# 51_MCU_Development_board.net
KiCad netlist of a schematic drawn in Altium Designer
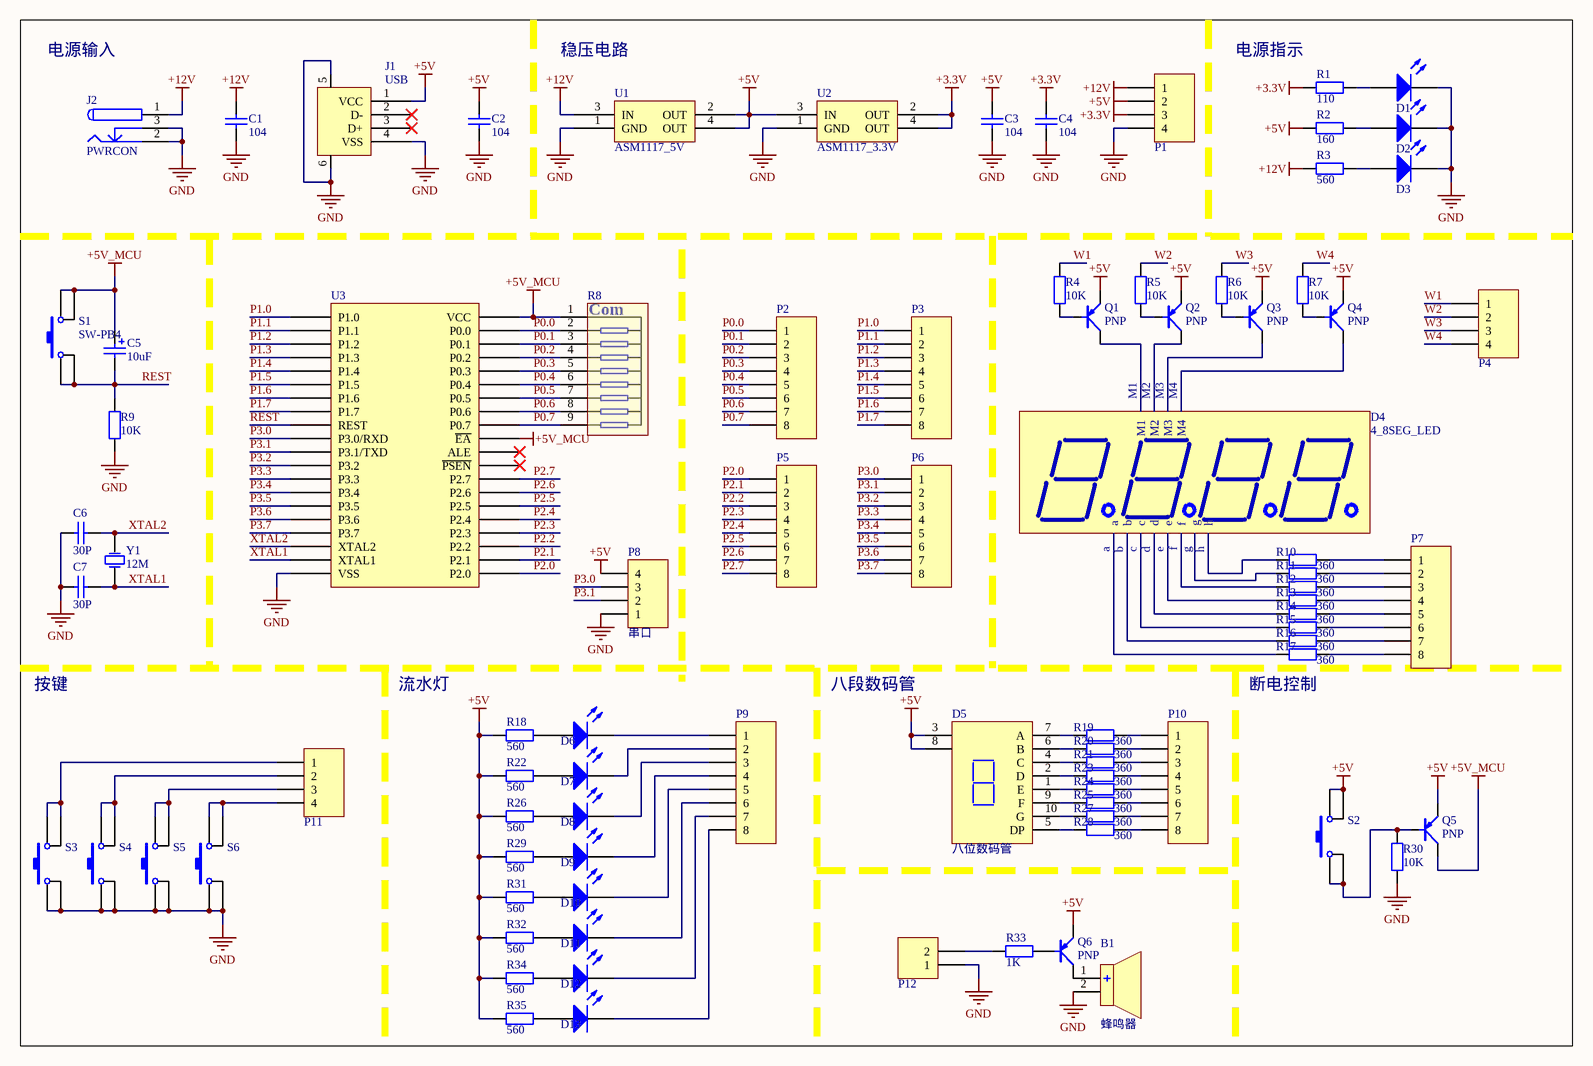
[diagram p0: 51 MCU Development board.SchDoc]

(export (version "E")
  (design (tool "Eeschema 10.0.6"))
  (components
    (comp (ref "B1")
      (value "蜂鸣器")
      (footprint "蜂鸣器")
      (libsource (lib "51 MCU Development board") (part "蜂鸣器"))
    )
    (comp (ref "C1")
      (value "104")
      (footprint "C-RAD-0805")
      (description "无极性电容")
      (fields (field (name "Comment") "Cap") (field (name "PUBLISHER") "Altium Limited"))
      (libsource (lib "常用库文件") (part "Cap"))
    )
    (comp (ref "C2")
      (value "104")
      (footprint "C-RAD-0805")
      (description "无极性电容")
      (fields (field (name "Comment") "Cap") (field (name "PUBLISHER") "Altium Limited"))
      (libsource (lib "常用库文件") (part "Cap"))
    )
    (comp (ref "C3")
      (value "104")
      (footprint "C-RAD-0805")
      (description "无极性电容")
      (fields (field (name "Comment") "Cap") (field (name "PUBLISHER") "Altium Limited"))
      (libsource (lib "常用库文件") (part "Cap"))
    )
    (comp (ref "C4")
      (value "104")
      (footprint "C-RAD-0805")
      (description "无极性电容")
      (fields (field (name "Comment") "Cap") (field (name "PUBLISHER") "Altium Limited"))
      (libsource (lib "常用库文件") (part "Cap"))
    )
    (comp (ref "C5")
      (value "10uF")
      (footprint "10UF")
      (description "Polarized Capacitor (Radial)")
      (fields (field (name "Comment") "Cap Pol1") (field (name "PUBLISHER") "Altium Limited"))
      (libsource (lib "51 MCU Development board") (part "Cap Pol1"))
    )
    (comp (ref "C6")
      (value "30P")
      (footprint "C-RAD")
      (description "无极性电容")
      (fields (field (name "Comment") "Cap") (field (name "PUBLISHER") "Altium Limited"))
      (libsource (lib "常用库文件") (part "Cap"))
    )
    (comp (ref "C7")
      (value "30P")
      (footprint "C-RAD")
      (description "无极性电容")
      (fields (field (name "Comment") "Cap") (field (name "PUBLISHER") "Altium Limited"))
      (libsource (lib "常用库文件") (part "Cap"))
    )
    (comp (ref "D1")
      (value "LED0")
      (footprint "LED_0805")
      (description "发光二极管")
      (fields (field (name "PUBLISHER") "Altium Limited"))
      (libsource (lib "常用库文件") (part "LED0"))
    )
    (comp (ref "D2")
      (value "LED0")
      (footprint "LED_0805")
      (description "发光二极管")
      (fields (field (name "PUBLISHER") "Altium Limited"))
      (libsource (lib "常用库文件") (part "LED0"))
    )
    (comp (ref "D3")
      (value "LED0")
      (footprint "LED_0805")
      (description "发光二极管")
      (fields (field (name "PUBLISHER") "Altium Limited"))
      (libsource (lib "常用库文件") (part "LED0"))
    )
    (comp (ref "D4")
      (value "4_8SEG_LED")
      (footprint "4BIT_8SEG_LED")
      (libsource (lib "51 MCU Development board") (part "4_8SEG_LED"))
    )
    (comp (ref "D5")
      (value "八位数码管")
      (footprint "八位数码管")
      (libsource (lib "51 MCU Development board") (part "八位数码管"))
    )
    (comp (ref "D6")
      (value "LED0")
      (footprint "LED直插")
      (description "发光二极管")
      (fields (field (name "PUBLISHER") "Altium Limited"))
      (libsource (lib "常用库文件") (part "LED0"))
    )
    (comp (ref "D7")
      (value "LED0")
      (footprint "LED直插")
      (description "发光二极管")
      (fields (field (name "PUBLISHER") "Altium Limited"))
      (libsource (lib "常用库文件") (part "LED0"))
    )
    (comp (ref "D8")
      (value "LED0")
      (footprint "LED直插")
      (description "发光二极管")
      (fields (field (name "PUBLISHER") "Altium Limited"))
      (libsource (lib "常用库文件") (part "LED0"))
    )
    (comp (ref "D9")
      (value "LED0")
      (footprint "LED直插")
      (description "发光二极管")
      (fields (field (name "PUBLISHER") "Altium Limited"))
      (libsource (lib "常用库文件") (part "LED0"))
    )
    (comp (ref "D10")
      (value "LED0")
      (footprint "LED直插")
      (description "发光二极管")
      (fields (field (name "PUBLISHER") "Altium Limited"))
      (libsource (lib "常用库文件") (part "LED0"))
    )
    (comp (ref "D11")
      (value "LED0")
      (footprint "LED直插")
      (description "发光二极管")
      (fields (field (name "PUBLISHER") "Altium Limited"))
      (libsource (lib "常用库文件") (part "LED0"))
    )
    (comp (ref "D12")
      (value "LED0")
      (footprint "LED直插")
      (description "发光二极管")
      (fields (field (name "PUBLISHER") "Altium Limited"))
      (libsource (lib "常用库文件") (part "LED0"))
    )
    (comp (ref "D13")
      (value "LED0")
      (footprint "LED直插")
      (description "发光二极管")
      (fields (field (name "PUBLISHER") "Altium Limited"))
      (libsource (lib "常用库文件") (part "LED0"))
    )
    (comp (ref "J1")
      (value "USB")
      (footprint "USB_A1")
      (description "USB接口")
      (libsource (lib "常用库文件") (part "USB"))
    )
    (comp (ref "J2")
      (value "PWRCON")
      (footprint "DC-005")
      (description "直流电源端子")
      (fields (field (name "PUBLISHER") "Altium Limited"))
      (libsource (lib "常用库文件") (part "PWRCON"))
    )
    (comp (ref "P1")
      (value "Header 4")
      (footprint "HDR4X1_A")
      (description "接插件")
      (fields (field (name "PUBLISHER") "Altium Limited"))
      (libsource (lib "常用库文件") (part "Header 4"))
    )
    (comp (ref "P2")
      (value "Header 8")
      (footprint "HDR1X8")
      (description "Header, 8-Pin")
      (fields (field (name "PUBLISHER") "Altium Limited"))
      (libsource (lib "Miscellaneous Connectors") (part "Header 8"))
    )
    (comp (ref "P3")
      (value "Header 8")
      (footprint "HDR1X8")
      (description "Header, 8-Pin")
      (fields (field (name "PUBLISHER") "Altium Limited"))
      (libsource (lib "Miscellaneous Connectors") (part "Header 8"))
    )
    (comp (ref "P4")
      (value "Header 4")
      (footprint "HDR4X1_A")
      (description "接插件")
      (fields (field (name "PUBLISHER") "Altium Limited"))
      (libsource (lib "常用库文件") (part "Header 4"))
    )
    (comp (ref "P5")
      (value "Header 8")
      (footprint "HDR1X8")
      (description "Header, 8-Pin")
      (fields (field (name "PUBLISHER") "Altium Limited"))
      (libsource (lib "Miscellaneous Connectors") (part "Header 8"))
    )
    (comp (ref "P6")
      (value "Header 8")
      (footprint "HDR1X8")
      (description "Header, 8-Pin")
      (fields (field (name "PUBLISHER") "Altium Limited"))
      (libsource (lib "Miscellaneous Connectors") (part "Header 8"))
    )
    (comp (ref "P7")
      (value "Header 8")
      (footprint "HDR1X8")
      (description "Header, 8-Pin")
      (fields (field (name "PUBLISHER") "Altium Limited"))
      (libsource (lib "Miscellaneous Connectors") (part "Header 8"))
    )
    (comp (ref "P8")
      (value "串口")
      (footprint "HDR4X1_A")
      (description "接插件")
      (fields (field (name "PUBLISHER") "Altium Limited"))
      (libsource (lib "") (part "Header 4_1"))
    )
    (comp (ref "P9")
      (value "Header 8")
      (footprint "HDR1X8")
      (description "Header, 8-Pin")
      (fields (field (name "PUBLISHER") "Altium Limited"))
      (libsource (lib "Miscellaneous Connectors") (part "Header 8"))
    )
    (comp (ref "P10")
      (value "Header 8")
      (footprint "HDR1X8")
      (description "Header, 8-Pin")
      (fields (field (name "PUBLISHER") "Altium Limited"))
      (libsource (lib "Miscellaneous Connectors") (part "Header 8"))
    )
    (comp (ref "P11")
      (value "Header 4")
      (footprint "HDR4X1_A")
      (description "接插件")
      (fields (field (name "PUBLISHER") "Altium Limited"))
      (libsource (lib "常用库文件") (part "Header 4"))
    )
    (comp (ref "P12")
      (value "Header 2")
      (footprint "HDR2X1_A")
      (description "接插件")
      (fields (field (name "PUBLISHER") "Altium Limited"))
      (libsource (lib "常用库文件") (part "Header 2"))
    )
    (comp (ref "Q1")
      (value "PNP")
      (footprint "TO-92")
      (libsource (lib "51 MCU Development board") (part "PNP"))
    )
    (comp (ref "Q2")
      (value "PNP")
      (footprint "TO-92")
      (libsource (lib "51 MCU Development board") (part "PNP"))
    )
    (comp (ref "Q3")
      (value "PNP")
      (footprint "TO-92")
      (libsource (lib "51 MCU Development board") (part "PNP"))
    )
    (comp (ref "Q4")
      (value "PNP")
      (footprint "TO-92")
      (libsource (lib "51 MCU Development board") (part "PNP"))
    )
    (comp (ref "Q5")
      (value "PNP")
      (footprint "TO-92")
      (libsource (lib "51 MCU Development board") (part "PNP"))
    )
    (comp (ref "Q6")
      (value "PNP")
      (footprint "TO-92")
      (libsource (lib "51 MCU Development board") (part "PNP"))
    )
    (comp (ref "R1")
      (value "110")
      (footprint "0805-1")
      (description "贴片电阻")
      (fields (field (name "Comment") "Res1") (field (name "PUBLISHER") "Altium Limited"))
      (libsource (lib "常用库文件") (part "Res1"))
    )
    (comp (ref "R2")
      (value "160")
      (footprint "0805-1")
      (description "贴片电阻")
      (fields (field (name "Comment") "Res1") (field (name "PUBLISHER") "Altium Limited"))
      (libsource (lib "常用库文件") (part "Res1"))
    )
    (comp (ref "R3")
      (value "560")
      (footprint "0805-1")
      (description "贴片电阻")
      (fields (field (name "Comment") "Res1") (field (name "PUBLISHER") "Altium Limited"))
      (libsource (lib "常用库文件") (part "Res1"))
    )
    (comp (ref "R4")
      (value "10K")
      (footprint "0805-1")
      (description "贴片电阻")
      (fields (field (name "Comment") "Res1") (field (name "PUBLISHER") "Altium Limited"))
      (libsource (lib "") (part "Res1_1"))
    )
    (comp (ref "R5")
      (value "10K")
      (footprint "0805-1")
      (description "贴片电阻")
      (fields (field (name "Comment") "Res1") (field (name "PUBLISHER") "Altium Limited"))
      (libsource (lib "") (part "Res1_1"))
    )
    (comp (ref "R6")
      (value "10K")
      (footprint "0805-1")
      (description "贴片电阻")
      (fields (field (name "Comment") "Res1") (field (name "PUBLISHER") "Altium Limited"))
      (libsource (lib "") (part "Res1_1"))
    )
    (comp (ref "R7")
      (value "10K")
      (footprint "0805-1")
      (description "贴片电阻")
      (fields (field (name "Comment") "Res1") (field (name "PUBLISHER") "Altium Limited"))
      (libsource (lib "") (part "Res1_1"))
    )
    (comp (ref "R8")
      (value "RES10")
      (footprint "SIP9")
      (libsource (lib "51 MCU Development board") (part "RES10"))
    )
    (comp (ref "R9")
      (value "10K")
      (footprint "0805-1")
      (description "贴片电阻")
      (fields (field (name "Comment") "Res1") (field (name "PUBLISHER") "Altium Limited"))
      (libsource (lib "") (part "Res1_1"))
    )
    (comp (ref "R10")
      (value "360")
      (footprint "0805-1")
      (description "贴片电阻")
      (fields (field (name "Comment") "Res1") (field (name "PUBLISHER") "Altium Limited"))
      (libsource (lib "") (part "Res1_2"))
    )
    (comp (ref "R11")
      (value "360")
      (footprint "0805-1")
      (description "贴片电阻")
      (fields (field (name "Comment") "Res1") (field (name "PUBLISHER") "Altium Limited"))
      (libsource (lib "") (part "Res1_2"))
    )
    (comp (ref "R12")
      (value "360")
      (footprint "0805-1")
      (description "贴片电阻")
      (fields (field (name "Comment") "Res1") (field (name "PUBLISHER") "Altium Limited"))
      (libsource (lib "") (part "Res1_2"))
    )
    (comp (ref "R13")
      (value "360")
      (footprint "0805-1")
      (description "贴片电阻")
      (fields (field (name "Comment") "Res1") (field (name "PUBLISHER") "Altium Limited"))
      (libsource (lib "") (part "Res1_2"))
    )
    (comp (ref "R14")
      (value "360")
      (footprint "0805-1")
      (description "贴片电阻")
      (fields (field (name "Comment") "Res1") (field (name "PUBLISHER") "Altium Limited"))
      (libsource (lib "") (part "Res1_2"))
    )
    (comp (ref "R15")
      (value "360")
      (footprint "0805-1")
      (description "贴片电阻")
      (fields (field (name "Comment") "Res1") (field (name "PUBLISHER") "Altium Limited"))
      (libsource (lib "") (part "Res1_2"))
    )
    (comp (ref "R16")
      (value "360")
      (footprint "0805-1")
      (description "贴片电阻")
      (fields (field (name "Comment") "Res1") (field (name "PUBLISHER") "Altium Limited"))
      (libsource (lib "") (part "Res1_2"))
    )
    (comp (ref "R17")
      (value "360")
      (footprint "0805-1")
      (description "贴片电阻")
      (fields (field (name "Comment") "Res1") (field (name "PUBLISHER") "Altium Limited"))
      (libsource (lib "") (part "Res1_2"))
    )
    (comp (ref "R18")
      (value "560")
      (footprint "0805-1")
      (description "贴片电阻")
      (fields (field (name "Comment") "Res1") (field (name "PUBLISHER") "Altium Limited"))
      (libsource (lib "常用库文件") (part "Res1"))
    )
    (comp (ref "R19")
      (value "360")
      (footprint "0805-1")
      (description "贴片电阻")
      (fields (field (name "Comment") "Res1") (field (name "PUBLISHER") "Altium Limited"))
      (libsource (lib "") (part "Res1_2"))
    )
    (comp (ref "R20")
      (value "360")
      (footprint "0805-1")
      (description "贴片电阻")
      (fields (field (name "Comment") "Res1") (field (name "PUBLISHER") "Altium Limited"))
      (libsource (lib "") (part "Res1_2"))
    )
    (comp (ref "R21")
      (value "360")
      (footprint "0805-1")
      (description "贴片电阻")
      (fields (field (name "Comment") "Res1") (field (name "PUBLISHER") "Altium Limited"))
      (libsource (lib "") (part "Res1_2"))
    )
    (comp (ref "R22")
      (value "560")
      (footprint "0805-1")
      (description "贴片电阻")
      (fields (field (name "Comment") "Res1") (field (name "PUBLISHER") "Altium Limited"))
      (libsource (lib "常用库文件") (part "Res1"))
    )
    (comp (ref "R23")
      (value "360")
      (footprint "0805-1")
      (description "贴片电阻")
      (fields (field (name "Comment") "Res1") (field (name "PUBLISHER") "Altium Limited"))
      (libsource (lib "") (part "Res1_2"))
    )
    (comp (ref "R24")
      (value "360")
      (footprint "0805-1")
      (description "贴片电阻")
      (fields (field (name "Comment") "Res1") (field (name "PUBLISHER") "Altium Limited"))
      (libsource (lib "") (part "Res1_2"))
    )
    (comp (ref "R25")
      (value "360")
      (footprint "0805-1")
      (description "贴片电阻")
      (fields (field (name "Comment") "Res1") (field (name "PUBLISHER") "Altium Limited"))
      (libsource (lib "") (part "Res1_2"))
    )
    (comp (ref "R26")
      (value "560")
      (footprint "0805-1")
      (description "贴片电阻")
      (fields (field (name "Comment") "Res1") (field (name "PUBLISHER") "Altium Limited"))
      (libsource (lib "常用库文件") (part "Res1"))
    )
    (comp (ref "R27")
      (value "360")
      (footprint "0805-1")
      (description "贴片电阻")
      (fields (field (name "Comment") "Res1") (field (name "PUBLISHER") "Altium Limited"))
      (libsource (lib "") (part "Res1_2"))
    )
    (comp (ref "R28")
      (value "360")
      (footprint "0805-1")
      (description "贴片电阻")
      (fields (field (name "Comment") "Res1") (field (name "PUBLISHER") "Altium Limited"))
      (libsource (lib "") (part "Res1_2"))
    )
    (comp (ref "R29")
      (value "560")
      (footprint "0805-1")
      (description "贴片电阻")
      (fields (field (name "Comment") "Res1") (field (name "PUBLISHER") "Altium Limited"))
      (libsource (lib "常用库文件") (part "Res1"))
    )
    (comp (ref "R30")
      (value "10K")
      (footprint "0805-1")
      (description "贴片电阻")
      (fields (field (name "Comment") "Res1") (field (name "PUBLISHER") "Altium Limited"))
      (libsource (lib "") (part "Res1_1"))
    )
    (comp (ref "R31")
      (value "560")
      (footprint "0805-1")
      (description "贴片电阻")
      (fields (field (name "Comment") "Res1") (field (name "PUBLISHER") "Altium Limited"))
      (libsource (lib "常用库文件") (part "Res1"))
    )
    (comp (ref "R32")
      (value "560")
      (footprint "0805-1")
      (description "贴片电阻")
      (fields (field (name "Comment") "Res1") (field (name "PUBLISHER") "Altium Limited"))
      (libsource (lib "常用库文件") (part "Res1"))
    )
    (comp (ref "R33")
      (value "1K")
      (footprint "0805-1")
      (description "贴片电阻")
      (fields (field (name "Comment") "Res1") (field (name "PUBLISHER") "Altium Limited"))
      (libsource (lib "") (part "Res1_2"))
    )
    (comp (ref "R34")
      (value "560")
      (footprint "0805-1")
      (description "贴片电阻")
      (fields (field (name "Comment") "Res1") (field (name "PUBLISHER") "Altium Limited"))
      (libsource (lib "常用库文件") (part "Res1"))
    )
    (comp (ref "R35")
      (value "560")
      (footprint "0805-1")
      (description "贴片电阻")
      (fields (field (name "Comment") "Res1") (field (name "PUBLISHER") "Altium Limited"))
      (libsource (lib "常用库文件") (part "Res1"))
    )
    (comp (ref "S1")
      (value "SW-PB4")
      (footprint "AN66")
      (description "微动开关")
      (fields (field (name "PUBLISHER") "Altium Limited"))
      (libsource (lib "常用库文件") (part "SW-PB4"))
    )
    (comp (ref "S2")
      (value "SW-PB4")
      (footprint "AN66")
      (description "微动开关")
      (fields (field (name "PUBLISHER") "Altium Limited"))
      (libsource (lib "常用库文件") (part "SW-PB4"))
    )
    (comp (ref "S3")
      (value "SW-PB4")
      (footprint "AN66")
      (description "微动开关")
      (fields (field (name "PUBLISHER") "Altium Limited"))
      (libsource (lib "常用库文件") (part "SW-PB4"))
    )
    (comp (ref "S4")
      (value "SW-PB4")
      (footprint "AN66")
      (description "微动开关")
      (fields (field (name "PUBLISHER") "Altium Limited"))
      (libsource (lib "常用库文件") (part "SW-PB4"))
    )
    (comp (ref "S5")
      (value "SW-PB4")
      (footprint "AN66")
      (description "微动开关")
      (fields (field (name "PUBLISHER") "Altium Limited"))
      (libsource (lib "常用库文件") (part "SW-PB4"))
    )
    (comp (ref "S6")
      (value "SW-PB4")
      (footprint "AN66")
      (description "微动开关")
      (fields (field (name "PUBLISHER") "Altium Limited"))
      (libsource (lib "常用库文件") (part "SW-PB4"))
    )
    (comp (ref "U1")
      (value "ASM1117_5V")
      (footprint "SOT-223")
      (description "3.3V稳压芯片")
      (libsource (lib "常用库文件") (part "ASM1117"))
    )
    (comp (ref "U2")
      (value "ASM1117_3.3V")
      (footprint "SOT-223")
      (description "3.3V稳压芯片")
      (libsource (lib "常用库文件") (part "ASM1117"))
    )
    (comp (ref "U3")
      (value "STC89C52RC")
      (footprint "DIP-40W")
      (libsource (lib "51 MCU Development board") (part "STC89C52RC"))
    )
    (comp (ref "Y1")
      (value "12M")
      (footprint "X-HC49U")
      (description "晶振")
      (fields (field (name "Comment") "XTAL") (field (name "PUBLISHER") "Altium Limited"))
      (libsource (lib "常用库文件") (part "XTAL"))
    )
  )
  (nets
    (net (code "1") (name "+3.3V") (class "Default")
      (node (ref "C4") (pin "2") (pinfunction "2_2") (pintype "passive"))
      (node (ref "P1") (pin "3") (pinfunction "3_3") (pintype "passive"))
      (node (ref "R1") (pin "1") (pinfunction "1_1") (pintype "passive"))
      (node (ref "U2") (pin "2") (pinfunction "OUT_2") (pintype "passive"))
      (node (ref "U2") (pin "4") (pinfunction "OUT_4") (pintype "passive"))
    )
    (net (code "2") (name "+5V") (class "Default")
      (node (ref "C2") (pin "2") (pinfunction "2_2") (pintype "passive"))
      (node (ref "C3") (pin "2") (pinfunction "2_2") (pintype "passive"))
      (node (ref "D5") (pin "3") (pinfunction "3_3") (pintype "passive"))
      (node (ref "D5") (pin "8") (pinfunction "8_8") (pintype "passive"))
      (node (ref "J1") (pin "1") (pinfunction "VCC_1") (pintype "passive"))
      (node (ref "P1") (pin "2") (pinfunction "2_2") (pintype "passive"))
      (node (ref "P8") (pin "4") (pinfunction "4_4") (pintype "passive"))
      (node (ref "Q1") (pin "E") (pinfunction "e_E") (pintype "passive"))
      (node (ref "Q2") (pin "E") (pinfunction "e_E") (pintype "passive"))
      (node (ref "Q3") (pin "E") (pinfunction "e_E") (pintype "passive"))
      (node (ref "Q4") (pin "E") (pinfunction "e_E") (pintype "passive"))
      (node (ref "Q5") (pin "E") (pinfunction "e_E") (pintype "passive"))
      (node (ref "Q6") (pin "E") (pinfunction "e_E") (pintype "passive"))
      (node (ref "R18") (pin "1") (pinfunction "1_1") (pintype "passive"))
      (node (ref "R2") (pin "1") (pinfunction "1_1") (pintype "passive"))
      (node (ref "R22") (pin "1") (pinfunction "1_1") (pintype "passive"))
      (node (ref "R26") (pin "1") (pinfunction "1_1") (pintype "passive"))
      (node (ref "R29") (pin "1") (pinfunction "1_1") (pintype "passive"))
      (node (ref "R31") (pin "1") (pinfunction "1_1") (pintype "passive"))
      (node (ref "R32") (pin "1") (pinfunction "1_1") (pintype "passive"))
      (node (ref "R34") (pin "1") (pinfunction "1_1") (pintype "passive"))
      (node (ref "R35") (pin "1") (pinfunction "1_1") (pintype "passive"))
      (node (ref "S2") (pin "2") (pinfunction "2_2") (pintype "passive"))
      (node (ref "S2") (pin "3") (pinfunction "3_3") (pintype "passive"))
      (node (ref "U1") (pin "2") (pinfunction "OUT_2") (pintype "passive"))
      (node (ref "U1") (pin "4") (pinfunction "OUT_4") (pintype "passive"))
      (node (ref "U2") (pin "3") (pinfunction "IN_3") (pintype "passive"))
    )
    (net (code "3") (name "+5V_MCU") (class "Default")
      (node (ref "C5") (pin "1") (pinfunction "1_1") (pintype "passive"))
      (node (ref "Q5") (pin "C") (pinfunction "c_C") (pintype "passive"))
      (node (ref "R8") (pin "1") (pinfunction "Com_1") (pintype "passive"))
      (node (ref "S1") (pin "2") (pinfunction "2_2") (pintype "passive"))
      (node (ref "S1") (pin "3") (pinfunction "3_3") (pintype "passive"))
      (node (ref "U3") (pin "31") (pinfunction "~{EA}_31") (pintype "power_in"))
      (node (ref "U3") (pin "40") (pinfunction "VCC_40") (pintype "power_in"))
    )
    (net (code "4") (name "+12V") (class "Default")
      (node (ref "C1") (pin "2") (pinfunction "2_2") (pintype "passive"))
      (node (ref "J2") (pin "1") (pinfunction "1_1") (pintype "power_in"))
      (node (ref "P1") (pin "1") (pinfunction "1_1") (pintype "passive"))
      (node (ref "R3") (pin "1") (pinfunction "1_1") (pintype "passive"))
      (node (ref "U1") (pin "3") (pinfunction "IN_3") (pintype "passive"))
    )
    (net (code "5") (name "/P0.0") (class "Default")
      (node (ref "P2") (pin "1") (pinfunction "1_1") (pintype "passive"))
      (node (ref "R8") (pin "2") (pinfunction "2_2") (pintype "passive"))
      (node (ref "U3") (pin "39") (pinfunction "P0.0_39") (pintype "power_in"))
    )
    (net (code "6") (name "/P0.1") (class "Default")
      (node (ref "P2") (pin "2") (pinfunction "2_2") (pintype "passive"))
      (node (ref "R8") (pin "3") (pinfunction "3_3") (pintype "passive"))
      (node (ref "U3") (pin "38") (pinfunction "P0.1_38") (pintype "power_in"))
    )
    (net (code "7") (name "/P0.2") (class "Default")
      (node (ref "P2") (pin "3") (pinfunction "3_3") (pintype "passive"))
      (node (ref "R8") (pin "4") (pinfunction "4_4") (pintype "passive"))
      (node (ref "U3") (pin "37") (pinfunction "P0.2_37") (pintype "power_in"))
    )
    (net (code "8") (name "/P0.3") (class "Default")
      (node (ref "P2") (pin "4") (pinfunction "4_4") (pintype "passive"))
      (node (ref "R8") (pin "5") (pinfunction "5_5") (pintype "passive"))
      (node (ref "U3") (pin "36") (pinfunction "P0.3_36") (pintype "power_in"))
    )
    (net (code "9") (name "/P0.4") (class "Default")
      (node (ref "P2") (pin "5") (pinfunction "5_5") (pintype "passive"))
      (node (ref "R8") (pin "6") (pinfunction "6_6") (pintype "passive"))
      (node (ref "U3") (pin "35") (pinfunction "P0.4_35") (pintype "power_in"))
    )
    (net (code "10") (name "/P0.5") (class "Default")
      (node (ref "P2") (pin "6") (pinfunction "6_6") (pintype "passive"))
      (node (ref "R8") (pin "7") (pinfunction "7_7") (pintype "passive"))
      (node (ref "U3") (pin "34") (pinfunction "P0.5_34") (pintype "power_in"))
    )
    (net (code "11") (name "/P0.6") (class "Default")
      (node (ref "P2") (pin "7") (pinfunction "7_7") (pintype "passive"))
      (node (ref "R8") (pin "8") (pinfunction "8_8") (pintype "passive"))
      (node (ref "U3") (pin "33") (pinfunction "P0.6_33") (pintype "power_in"))
    )
    (net (code "12") (name "/P0.7") (class "Default")
      (node (ref "P2") (pin "8") (pinfunction "8_8") (pintype "passive"))
      (node (ref "R8") (pin "9") (pinfunction "9_9") (pintype "passive"))
      (node (ref "U3") (pin "32") (pinfunction "P0.7_32") (pintype "power_in"))
    )
    (net (code "13") (name "/P1.0") (class "Default")
      (node (ref "P3") (pin "1") (pinfunction "1_1") (pintype "passive"))
      (node (ref "U3") (pin "1") (pinfunction "P1.0_1") (pintype "power_in"))
    )
    (net (code "14") (name "/P1.1") (class "Default")
      (node (ref "P3") (pin "2") (pinfunction "2_2") (pintype "passive"))
      (node (ref "U3") (pin "2") (pinfunction "P1.1_2") (pintype "power_in"))
    )
    (net (code "15") (name "/P1.2") (class "Default")
      (node (ref "P3") (pin "3") (pinfunction "3_3") (pintype "passive"))
      (node (ref "U3") (pin "3") (pinfunction "P1.2_3") (pintype "power_in"))
    )
    (net (code "16") (name "/P1.3") (class "Default")
      (node (ref "P3") (pin "4") (pinfunction "4_4") (pintype "passive"))
      (node (ref "U3") (pin "4") (pinfunction "P1.3_4") (pintype "power_in"))
    )
    (net (code "17") (name "/P1.4") (class "Default")
      (node (ref "P3") (pin "5") (pinfunction "5_5") (pintype "passive"))
      (node (ref "U3") (pin "5") (pinfunction "P1.4_5") (pintype "power_in"))
    )
    (net (code "18") (name "/P1.5") (class "Default")
      (node (ref "P3") (pin "6") (pinfunction "6_6") (pintype "passive"))
      (node (ref "U3") (pin "6") (pinfunction "P1.5_6") (pintype "power_in"))
    )
    (net (code "19") (name "/P1.6") (class "Default")
      (node (ref "P3") (pin "7") (pinfunction "7_7") (pintype "passive"))
      (node (ref "U3") (pin "7") (pinfunction "P1.6_7") (pintype "power_in"))
    )
    (net (code "20") (name "/P1.7") (class "Default")
      (node (ref "P3") (pin "8") (pinfunction "8_8") (pintype "passive"))
      (node (ref "U3") (pin "8") (pinfunction "P1.7_8") (pintype "power_in"))
    )
    (net (code "21") (name "/P2.0") (class "Default")
      (node (ref "P5") (pin "1") (pinfunction "1_1") (pintype "passive"))
      (node (ref "U3") (pin "21") (pinfunction "P2.0_21") (pintype "power_in"))
    )
    (net (code "22") (name "/P2.1") (class "Default")
      (node (ref "P5") (pin "2") (pinfunction "2_2") (pintype "passive"))
      (node (ref "U3") (pin "22") (pinfunction "P2.1_22") (pintype "power_in"))
    )
    (net (code "23") (name "/P2.2") (class "Default")
      (node (ref "P5") (pin "3") (pinfunction "3_3") (pintype "passive"))
      (node (ref "U3") (pin "23") (pinfunction "P2.2_23") (pintype "power_in"))
    )
    (net (code "24") (name "/P2.3") (class "Default")
      (node (ref "P5") (pin "4") (pinfunction "4_4") (pintype "passive"))
      (node (ref "U3") (pin "24") (pinfunction "P2.3_24") (pintype "power_in"))
    )
    (net (code "25") (name "/P2.4") (class "Default")
      (node (ref "P5") (pin "5") (pinfunction "5_5") (pintype "passive"))
      (node (ref "U3") (pin "25") (pinfunction "P2.4_25") (pintype "power_in"))
    )
    (net (code "26") (name "/P2.5") (class "Default")
      (node (ref "P5") (pin "6") (pinfunction "6_6") (pintype "passive"))
      (node (ref "U3") (pin "26") (pinfunction "P2.5_26") (pintype "power_in"))
    )
    (net (code "27") (name "/P2.6") (class "Default")
      (node (ref "P5") (pin "7") (pinfunction "7_7") (pintype "passive"))
      (node (ref "U3") (pin "27") (pinfunction "P2.6_27") (pintype "power_in"))
    )
    (net (code "28") (name "/P2.7") (class "Default")
      (node (ref "P5") (pin "8") (pinfunction "8_8") (pintype "passive"))
      (node (ref "U3") (pin "28") (pinfunction "P2.7_28") (pintype "power_in"))
    )
    (net (code "29") (name "/P3.0") (class "Default")
      (node (ref "P6") (pin "1") (pinfunction "1_1") (pintype "passive"))
      (node (ref "P8") (pin "3") (pinfunction "3_3") (pintype "passive"))
      (node (ref "U3") (pin "10") (pinfunction "P3.0/RXD_10") (pintype "power_in"))
    )
    (net (code "30") (name "/P3.1") (class "Default")
      (node (ref "P6") (pin "2") (pinfunction "2_2") (pintype "passive"))
      (node (ref "P8") (pin "2") (pinfunction "2_2") (pintype "passive"))
      (node (ref "U3") (pin "11") (pinfunction "P3.1/TXD_11") (pintype "power_in"))
    )
    (net (code "31") (name "/P3.2") (class "Default")
      (node (ref "P6") (pin "3") (pinfunction "3_3") (pintype "passive"))
      (node (ref "U3") (pin "12") (pinfunction "P3.2_12") (pintype "power_in"))
    )
    (net (code "32") (name "/P3.3") (class "Default")
      (node (ref "P6") (pin "4") (pinfunction "4_4") (pintype "passive"))
      (node (ref "U3") (pin "13") (pinfunction "P3.3_13") (pintype "power_in"))
    )
    (net (code "33") (name "/P3.4") (class "Default")
      (node (ref "P6") (pin "5") (pinfunction "5_5") (pintype "passive"))
      (node (ref "U3") (pin "14") (pinfunction "P3.4_14") (pintype "power_in"))
    )
    (net (code "34") (name "/P3.5") (class "Default")
      (node (ref "P6") (pin "6") (pinfunction "6_6") (pintype "passive"))
      (node (ref "U3") (pin "15") (pinfunction "P3.5_15") (pintype "power_in"))
    )
    (net (code "35") (name "/P3.6") (class "Default")
      (node (ref "P6") (pin "7") (pinfunction "7_7") (pintype "passive"))
      (node (ref "U3") (pin "16") (pinfunction "P3.6_16") (pintype "power_in"))
    )
    (net (code "36") (name "/P3.7") (class "Default")
      (node (ref "P6") (pin "8") (pinfunction "8_8") (pintype "passive"))
      (node (ref "U3") (pin "17") (pinfunction "P3.7_17") (pintype "power_in"))
    )
    (net (code "37") (name "/REST") (class "Default")
      (node (ref "C5") (pin "2") (pinfunction "2_2") (pintype "passive"))
      (node (ref "R9") (pin "2") (pinfunction "2_2") (pintype "passive"))
      (node (ref "S1") (pin "1") (pinfunction "1_1") (pintype "passive"))
      (node (ref "S1") (pin "4") (pinfunction "4_4") (pintype "passive"))
      (node (ref "U3") (pin "9") (pinfunction "REST_9") (pintype "power_in"))
    )
    (net (code "38") (name "/W1") (class "Default")
      (node (ref "P4") (pin "1") (pinfunction "1_1") (pintype "passive"))
      (node (ref "R4") (pin "2") (pinfunction "2_2") (pintype "passive"))
    )
    (net (code "39") (name "/W2") (class "Default")
      (node (ref "P4") (pin "2") (pinfunction "2_2") (pintype "passive"))
      (node (ref "R5") (pin "2") (pinfunction "2_2") (pintype "passive"))
    )
    (net (code "40") (name "/W3") (class "Default")
      (node (ref "P4") (pin "3") (pinfunction "3_3") (pintype "passive"))
      (node (ref "R6") (pin "2") (pinfunction "2_2") (pintype "passive"))
    )
    (net (code "41") (name "/W4") (class "Default")
      (node (ref "P4") (pin "4") (pinfunction "4_4") (pintype "passive"))
      (node (ref "R7") (pin "2") (pinfunction "2_2") (pintype "passive"))
    )
    (net (code "42") (name "/XTAL1") (class "Default")
      (node (ref "C7") (pin "2") (pinfunction "2_2") (pintype "passive"))
      (node (ref "U3") (pin "19") (pinfunction "XTAL1_19") (pintype "power_in"))
      (node (ref "Y1") (pin "1") (pinfunction "OSC1_1") (pintype "passive"))
    )
    (net (code "43") (name "/XTAL2") (class "Default")
      (node (ref "C6") (pin "2") (pinfunction "2_2") (pintype "passive"))
      (node (ref "U3") (pin "18") (pinfunction "XTAL2_18") (pintype "power_in"))
      (node (ref "Y1") (pin "2") (pinfunction "OSC2_2") (pintype "passive"))
    )
    (net (code "44") (name "GND") (class "Default")
      (node (ref "B1") (pin "2") (pinfunction "2_2") (pintype "passive"))
      (node (ref "C1") (pin "1") (pinfunction "1_1") (pintype "passive"))
      (node (ref "C2") (pin "1") (pinfunction "1_1") (pintype "passive"))
      (node (ref "C3") (pin "1") (pinfunction "1_1") (pintype "passive"))
      (node (ref "C4") (pin "1") (pinfunction "1_1") (pintype "passive"))
      (node (ref "C6") (pin "1") (pinfunction "1_1") (pintype "passive"))
      (node (ref "C7") (pin "1") (pinfunction "1_1") (pintype "passive"))
      (node (ref "D1") (pin "2") (pinfunction "K_2") (pintype "passive"))
      (node (ref "D2") (pin "2") (pinfunction "K_2") (pintype "passive"))
      (node (ref "D3") (pin "2") (pinfunction "K_2") (pintype "passive"))
      (node (ref "J1") (pin "4") (pinfunction "VSS_4") (pintype "passive"))
      (node (ref "J1") (pin "5") (pinfunction "5_5") (pintype "passive"))
      (node (ref "J1") (pin "6") (pinfunction "6_6") (pintype "passive"))
      (node (ref "J2") (pin "2") (pinfunction "2_2") (pintype "power_in"))
      (node (ref "J2") (pin "3") (pinfunction "3_3") (pintype "power_in"))
      (node (ref "P1") (pin "4") (pinfunction "4_4") (pintype "passive"))
      (node (ref "P12") (pin "1") (pinfunction "1_1") (pintype "passive"))
      (node (ref "P8") (pin "1") (pinfunction "1_1") (pintype "passive"))
      (node (ref "R30") (pin "1") (pinfunction "1_1") (pintype "passive"))
      (node (ref "R9") (pin "1") (pinfunction "1_1") (pintype "passive"))
      (node (ref "S3") (pin "1") (pinfunction "1_1") (pintype "passive"))
      (node (ref "S3") (pin "4") (pinfunction "4_4") (pintype "passive"))
      (node (ref "S4") (pin "1") (pinfunction "1_1") (pintype "passive"))
      (node (ref "S4") (pin "4") (pinfunction "4_4") (pintype "passive"))
      (node (ref "S5") (pin "1") (pinfunction "1_1") (pintype "passive"))
      (node (ref "S5") (pin "4") (pinfunction "4_4") (pintype "passive"))
      (node (ref "S6") (pin "1") (pinfunction "1_1") (pintype "passive"))
      (node (ref "S6") (pin "4") (pinfunction "4_4") (pintype "passive"))
      (node (ref "U1") (pin "1") (pinfunction "GND_1") (pintype "passive"))
      (node (ref "U2") (pin "1") (pinfunction "GND_1") (pintype "passive"))
      (node (ref "U3") (pin "20") (pinfunction "VSS_20") (pintype "power_in"))
    )
    (net (code "45") (name "Net-(D1-A)") (class "Default")
      (node (ref "D1") (pin "1") (pinfunction "A_1") (pintype "passive"))
      (node (ref "R1") (pin "2") (pinfunction "2_2") (pintype "passive"))
    )
    (net (code "46") (name "Net-(D2-A)") (class "Default")
      (node (ref "D2") (pin "1") (pinfunction "A_1") (pintype "passive"))
      (node (ref "R2") (pin "2") (pinfunction "2_2") (pintype "passive"))
    )
    (net (code "47") (name "Net-(D3-A)") (class "Default")
      (node (ref "D3") (pin "1") (pinfunction "A_1") (pintype "passive"))
      (node (ref "R3") (pin "2") (pinfunction "2_2") (pintype "passive"))
    )
    (net (code "48") (name "Net-(D4-Pada)") (class "Default")
      (node (ref "D4") (pin "a") (pinfunction "a_a") (pintype "passive"))
      (node (ref "R17") (pin "2") (pinfunction "2_2") (pintype "passive"))
    )
    (net (code "49") (name "Net-(D4-Padb)") (class "Default")
      (node (ref "D4") (pin "b") (pinfunction "b_b") (pintype "passive"))
      (node (ref "R16") (pin "2") (pinfunction "2_2") (pintype "passive"))
    )
    (net (code "50") (name "Net-(D4-Padc)") (class "Default")
      (node (ref "D4") (pin "c") (pinfunction "c_c") (pintype "passive"))
      (node (ref "R15") (pin "2") (pinfunction "2_2") (pintype "passive"))
    )
    (net (code "51") (name "Net-(D4-Padd)") (class "Default")
      (node (ref "D4") (pin "d") (pinfunction "d_d") (pintype "passive"))
      (node (ref "R14") (pin "2") (pinfunction "2_2") (pintype "passive"))
    )
    (net (code "52") (name "Net-(D4-Pade)") (class "Default")
      (node (ref "D4") (pin "e") (pinfunction "e_e") (pintype "passive"))
      (node (ref "R13") (pin "2") (pinfunction "2_2") (pintype "passive"))
    )
    (net (code "53") (name "Net-(D4-Padf)") (class "Default")
      (node (ref "D4") (pin "f") (pinfunction "f_f") (pintype "passive"))
      (node (ref "R12") (pin "2") (pinfunction "2_2") (pintype "passive"))
    )
    (net (code "54") (name "Net-(D4-Padg)") (class "Default")
      (node (ref "D4") (pin "g") (pinfunction "g_g") (pintype "passive"))
      (node (ref "R11") (pin "2") (pinfunction "2_2") (pintype "passive"))
    )
    (net (code "55") (name "Net-(D4-Padh)") (class "Default")
      (node (ref "D4") (pin "h") (pinfunction "h_h") (pintype "passive"))
      (node (ref "R10") (pin "2") (pinfunction "2_2") (pintype "passive"))
    )
    (net (code "56") (name "Net-(D5-A)") (class "Default")
      (node (ref "D5") (pin "7") (pinfunction "A_7") (pintype "passive"))
      (node (ref "R19") (pin "2") (pinfunction "2_2") (pintype "passive"))
    )
    (net (code "57") (name "Net-(D5-B)") (class "Default")
      (node (ref "D5") (pin "6") (pinfunction "B_6") (pintype "passive"))
      (node (ref "R20") (pin "2") (pinfunction "2_2") (pintype "passive"))
    )
    (net (code "58") (name "Net-(D5-C)") (class "Default")
      (node (ref "D5") (pin "4") (pinfunction "C_4") (pintype "passive"))
      (node (ref "R21") (pin "2") (pinfunction "2_2") (pintype "passive"))
    )
    (net (code "59") (name "Net-(D5-D)") (class "Default")
      (node (ref "D5") (pin "2") (pinfunction "D_2") (pintype "passive"))
      (node (ref "R23") (pin "2") (pinfunction "2_2") (pintype "passive"))
    )
    (net (code "60") (name "Net-(D5-DP)") (class "Default")
      (node (ref "D5") (pin "5") (pinfunction "DP_5") (pintype "passive"))
      (node (ref "R28") (pin "2") (pinfunction "2_2") (pintype "passive"))
    )
    (net (code "61") (name "Net-(D5-E)") (class "Default")
      (node (ref "D5") (pin "1") (pinfunction "E_1") (pintype "passive"))
      (node (ref "R24") (pin "2") (pinfunction "2_2") (pintype "passive"))
    )
    (net (code "62") (name "Net-(D5-F)") (class "Default")
      (node (ref "D5") (pin "9") (pinfunction "F_9") (pintype "passive"))
      (node (ref "R25") (pin "2") (pinfunction "2_2") (pintype "passive"))
    )
    (net (code "63") (name "Net-(D5-G)") (class "Default")
      (node (ref "D5") (pin "10") (pinfunction "G_10") (pintype "passive"))
      (node (ref "R27") (pin "2") (pinfunction "2_2") (pintype "passive"))
    )
    (net (code "64") (name "Net-(D6-A)") (class "Default")
      (node (ref "D6") (pin "1") (pinfunction "A_1") (pintype "passive"))
      (node (ref "R18") (pin "2") (pinfunction "2_2") (pintype "passive"))
    )
    (net (code "65") (name "Net-(D6-K)") (class "Default")
      (node (ref "D6") (pin "2") (pinfunction "K_2") (pintype "passive"))
      (node (ref "P9") (pin "1") (pinfunction "1_1") (pintype "passive"))
    )
    (net (code "66") (name "Net-(D7-A)") (class "Default")
      (node (ref "D7") (pin "1") (pinfunction "A_1") (pintype "passive"))
      (node (ref "R22") (pin "2") (pinfunction "2_2") (pintype "passive"))
    )
    (net (code "67") (name "Net-(D7-K)") (class "Default")
      (node (ref "D7") (pin "2") (pinfunction "K_2") (pintype "passive"))
      (node (ref "P9") (pin "2") (pinfunction "2_2") (pintype "passive"))
    )
    (net (code "68") (name "Net-(D8-A)") (class "Default")
      (node (ref "D8") (pin "1") (pinfunction "A_1") (pintype "passive"))
      (node (ref "R26") (pin "2") (pinfunction "2_2") (pintype "passive"))
    )
    (net (code "69") (name "Net-(D8-K)") (class "Default")
      (node (ref "D8") (pin "2") (pinfunction "K_2") (pintype "passive"))
      (node (ref "P9") (pin "3") (pinfunction "3_3") (pintype "passive"))
    )
    (net (code "70") (name "Net-(D9-A)") (class "Default")
      (node (ref "D9") (pin "1") (pinfunction "A_1") (pintype "passive"))
      (node (ref "R29") (pin "2") (pinfunction "2_2") (pintype "passive"))
    )
    (net (code "71") (name "Net-(D9-K)") (class "Default")
      (node (ref "D9") (pin "2") (pinfunction "K_2") (pintype "passive"))
      (node (ref "P9") (pin "4") (pinfunction "4_4") (pintype "passive"))
    )
    (net (code "72") (name "Net-(D10-A)") (class "Default")
      (node (ref "D10") (pin "1") (pinfunction "A_1") (pintype "passive"))
      (node (ref "R31") (pin "2") (pinfunction "2_2") (pintype "passive"))
    )
    (net (code "73") (name "Net-(D10-K)") (class "Default")
      (node (ref "D10") (pin "2") (pinfunction "K_2") (pintype "passive"))
      (node (ref "P9") (pin "5") (pinfunction "5_5") (pintype "passive"))
    )
    (net (code "74") (name "Net-(D11-A)") (class "Default")
      (node (ref "D11") (pin "1") (pinfunction "A_1") (pintype "passive"))
      (node (ref "R32") (pin "2") (pinfunction "2_2") (pintype "passive"))
    )
    (net (code "75") (name "Net-(D11-K)") (class "Default")
      (node (ref "D11") (pin "2") (pinfunction "K_2") (pintype "passive"))
      (node (ref "P9") (pin "6") (pinfunction "6_6") (pintype "passive"))
    )
    (net (code "76") (name "Net-(D12-A)") (class "Default")
      (node (ref "D12") (pin "1") (pinfunction "A_1") (pintype "passive"))
      (node (ref "R34") (pin "2") (pinfunction "2_2") (pintype "passive"))
    )
    (net (code "77") (name "Net-(D12-K)") (class "Default")
      (node (ref "D12") (pin "2") (pinfunction "K_2") (pintype "passive"))
      (node (ref "P9") (pin "7") (pinfunction "7_7") (pintype "passive"))
    )
    (net (code "78") (name "Net-(D13-A)") (class "Default")
      (node (ref "D13") (pin "1") (pinfunction "A_1") (pintype "passive"))
      (node (ref "R35") (pin "2") (pinfunction "2_2") (pintype "passive"))
    )
    (net (code "79") (name "Net-(D13-K)") (class "Default")
      (node (ref "D13") (pin "2") (pinfunction "K_2") (pintype "passive"))
      (node (ref "P9") (pin "8") (pinfunction "8_8") (pintype "passive"))
    )
    (net (code "80") (name "Net-(P7-Pad1)") (class "Default")
      (node (ref "P7") (pin "1") (pinfunction "1_1") (pintype "passive"))
      (node (ref "R10") (pin "1") (pinfunction "1_1") (pintype "passive"))
    )
    (net (code "81") (name "Net-(P7-Pad2)") (class "Default")
      (node (ref "P7") (pin "2") (pinfunction "2_2") (pintype "passive"))
      (node (ref "R11") (pin "1") (pinfunction "1_1") (pintype "passive"))
    )
    (net (code "82") (name "Net-(P7-Pad3)") (class "Default")
      (node (ref "P7") (pin "3") (pinfunction "3_3") (pintype "passive"))
      (node (ref "R12") (pin "1") (pinfunction "1_1") (pintype "passive"))
    )
    (net (code "83") (name "Net-(P7-Pad4)") (class "Default")
      (node (ref "P7") (pin "4") (pinfunction "4_4") (pintype "passive"))
      (node (ref "R13") (pin "1") (pinfunction "1_1") (pintype "passive"))
    )
    (net (code "84") (name "Net-(P7-Pad5)") (class "Default")
      (node (ref "P7") (pin "5") (pinfunction "5_5") (pintype "passive"))
      (node (ref "R14") (pin "1") (pinfunction "1_1") (pintype "passive"))
    )
    (net (code "85") (name "Net-(P7-Pad6)") (class "Default")
      (node (ref "P7") (pin "6") (pinfunction "6_6") (pintype "passive"))
      (node (ref "R15") (pin "1") (pinfunction "1_1") (pintype "passive"))
    )
    (net (code "86") (name "Net-(P7-Pad7)") (class "Default")
      (node (ref "P7") (pin "7") (pinfunction "7_7") (pintype "passive"))
      (node (ref "R16") (pin "1") (pinfunction "1_1") (pintype "passive"))
    )
    (net (code "87") (name "Net-(P7-Pad8)") (class "Default")
      (node (ref "P7") (pin "8") (pinfunction "8_8") (pintype "passive"))
      (node (ref "R17") (pin "1") (pinfunction "1_1") (pintype "passive"))
    )
    (net (code "88") (name "Net-(P10-Pad1)") (class "Default")
      (node (ref "P10") (pin "1") (pinfunction "1_1") (pintype "passive"))
      (node (ref "R19") (pin "1") (pinfunction "1_1") (pintype "passive"))
    )
    (net (code "89") (name "Net-(P10-Pad2)") (class "Default")
      (node (ref "P10") (pin "2") (pinfunction "2_2") (pintype "passive"))
      (node (ref "R20") (pin "1") (pinfunction "1_1") (pintype "passive"))
    )
    (net (code "90") (name "Net-(P10-Pad3)") (class "Default")
      (node (ref "P10") (pin "3") (pinfunction "3_3") (pintype "passive"))
      (node (ref "R21") (pin "1") (pinfunction "1_1") (pintype "passive"))
    )
    (net (code "91") (name "Net-(P10-Pad4)") (class "Default")
      (node (ref "P10") (pin "4") (pinfunction "4_4") (pintype "passive"))
      (node (ref "R23") (pin "1") (pinfunction "1_1") (pintype "passive"))
    )
    (net (code "92") (name "Net-(P10-Pad5)") (class "Default")
      (node (ref "P10") (pin "5") (pinfunction "5_5") (pintype "passive"))
      (node (ref "R24") (pin "1") (pinfunction "1_1") (pintype "passive"))
    )
    (net (code "93") (name "Net-(P10-Pad6)") (class "Default")
      (node (ref "P10") (pin "6") (pinfunction "6_6") (pintype "passive"))
      (node (ref "R25") (pin "1") (pinfunction "1_1") (pintype "passive"))
    )
    (net (code "94") (name "Net-(P10-Pad7)") (class "Default")
      (node (ref "P10") (pin "7") (pinfunction "7_7") (pintype "passive"))
      (node (ref "R27") (pin "1") (pinfunction "1_1") (pintype "passive"))
    )
    (net (code "95") (name "Net-(P10-Pad8)") (class "Default")
      (node (ref "P10") (pin "8") (pinfunction "8_8") (pintype "passive"))
      (node (ref "R28") (pin "1") (pinfunction "1_1") (pintype "passive"))
    )
    (net (code "96") (name "Net-(P11-Pad1)") (class "Default")
      (node (ref "P11") (pin "1") (pinfunction "1_1") (pintype "passive"))
      (node (ref "S3") (pin "2") (pinfunction "2_2") (pintype "passive"))
      (node (ref "S3") (pin "3") (pinfunction "3_3") (pintype "passive"))
    )
    (net (code "97") (name "Net-(P11-Pad2)") (class "Default")
      (node (ref "P11") (pin "2") (pinfunction "2_2") (pintype "passive"))
      (node (ref "S4") (pin "2") (pinfunction "2_2") (pintype "passive"))
      (node (ref "S4") (pin "3") (pinfunction "3_3") (pintype "passive"))
    )
    (net (code "98") (name "Net-(P11-Pad3)") (class "Default")
      (node (ref "P11") (pin "3") (pinfunction "3_3") (pintype "passive"))
      (node (ref "S5") (pin "2") (pinfunction "2_2") (pintype "passive"))
      (node (ref "S5") (pin "3") (pinfunction "3_3") (pintype "passive"))
    )
    (net (code "99") (name "Net-(P11-Pad4)") (class "Default")
      (node (ref "P11") (pin "4") (pinfunction "4_4") (pintype "passive"))
      (node (ref "S6") (pin "2") (pinfunction "2_2") (pintype "passive"))
      (node (ref "S6") (pin "3") (pinfunction "3_3") (pintype "passive"))
    )
    (net (code "100") (name "Net-(P12-Pad2)") (class "Default")
      (node (ref "P12") (pin "2") (pinfunction "2_2") (pintype "passive"))
      (node (ref "R33") (pin "2") (pinfunction "2_2") (pintype "passive"))
    )
    (net (code "101") (name "Net-(Q1-b)") (class "Default")
      (node (ref "Q1") (pin "B") (pinfunction "b_B") (pintype "passive"))
      (node (ref "R4") (pin "1") (pinfunction "1_1") (pintype "passive"))
    )
    (net (code "102") (name "Net-(Q1-c)") (class "Default")
      (node (ref "D4") (pin "M1") (pinfunction "M1_M1") (pintype "passive"))
      (node (ref "Q1") (pin "C") (pinfunction "c_C") (pintype "passive"))
    )
    (net (code "103") (name "Net-(Q2-b)") (class "Default")
      (node (ref "Q2") (pin "B") (pinfunction "b_B") (pintype "passive"))
      (node (ref "R5") (pin "1") (pinfunction "1_1") (pintype "passive"))
    )
    (net (code "104") (name "Net-(Q2-c)") (class "Default")
      (node (ref "D4") (pin "M2") (pinfunction "M2_M2") (pintype "passive"))
      (node (ref "Q2") (pin "C") (pinfunction "c_C") (pintype "passive"))
    )
    (net (code "105") (name "Net-(Q3-b)") (class "Default")
      (node (ref "Q3") (pin "B") (pinfunction "b_B") (pintype "passive"))
      (node (ref "R6") (pin "1") (pinfunction "1_1") (pintype "passive"))
    )
    (net (code "106") (name "Net-(Q3-c)") (class "Default")
      (node (ref "D4") (pin "M3") (pinfunction "M3_M3") (pintype "passive"))
      (node (ref "Q3") (pin "C") (pinfunction "c_C") (pintype "passive"))
    )
    (net (code "107") (name "Net-(Q4-b)") (class "Default")
      (node (ref "Q4") (pin "B") (pinfunction "b_B") (pintype "passive"))
      (node (ref "R7") (pin "1") (pinfunction "1_1") (pintype "passive"))
    )
    (net (code "108") (name "Net-(Q4-c)") (class "Default")
      (node (ref "D4") (pin "M4") (pinfunction "M4_M4") (pintype "passive"))
      (node (ref "Q4") (pin "C") (pinfunction "c_C") (pintype "passive"))
    )
    (net (code "109") (name "Net-(Q5-b)") (class "Default")
      (node (ref "Q5") (pin "B") (pinfunction "b_B") (pintype "passive"))
      (node (ref "R30") (pin "2") (pinfunction "2_2") (pintype "passive"))
      (node (ref "S2") (pin "1") (pinfunction "1_1") (pintype "passive"))
      (node (ref "S2") (pin "4") (pinfunction "4_4") (pintype "passive"))
    )
    (net (code "110") (name "Net-(Q6-b)") (class "Default")
      (node (ref "Q6") (pin "B") (pinfunction "b_B") (pintype "passive"))
      (node (ref "R33") (pin "1") (pinfunction "1_1") (pintype "passive"))
    )
    (net (code "111") (name "Net-(Q6-c)") (class "Default")
      (node (ref "B1") (pin "1") (pinfunction "1_1") (pintype "passive"))
      (node (ref "Q6") (pin "C") (pinfunction "c_C") (pintype "passive"))
    )
    (net (code "112") (name "unconnected-(J1-D+-Pad3)") (class "Default")
      (node (ref "J1") (pin "3") (pinfunction "D+_3") (pintype "passive+no_connect"))
    )
    (net (code "113") (name "unconnected-(J1-D--Pad2)") (class "Default")
      (node (ref "J1") (pin "2") (pinfunction "D-_2") (pintype "passive+no_connect"))
    )
    (net (code "114") (name "unconnected-(U3-ALE-Pad30)") (class "Default")
      (node (ref "U3") (pin "30") (pinfunction "ALE_30") (pintype "power_in+no_connect"))
    )
    (net (code "115") (name "unconnected-(U3-~{PSEN}-Pad29)") (class "Default")
      (node (ref "U3") (pin "29") (pinfunction "~{PSEN}_29") (pintype "power_in+no_connect"))
    )
  )
)
